# feszduplazo.net
KiCad netlist of a schematic drawn in EAGLE
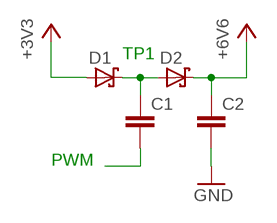
[diagram p0: schematic, sheet 1]

(export (version "E")
  (design (tool "Eeschema 10.0.6"))
  (components
    (comp (ref "C1")
      (value "C-EU050-024X044")
      (footprint "eagle-import:C050-024X044")
      (libsource (lib "eagle-import") (part "C-EU050-024X044"))
    )
    (comp (ref "C2")
      (value "C-EU050-024X044")
      (footprint "eagle-import:C050-024X044")
      (libsource (lib "eagle-import") (part "C-EU050-024X044"))
    )
    (comp (ref "D1")
      (value "1N5817-B")
      (footprint "eagle-import:DO41-7.6")
      (libsource (lib "eagle-import") (part "1N5817-B"))
    )
    (comp (ref "D2")
      (value "1N5817-B")
      (footprint "eagle-import:DO41-7.6")
      (libsource (lib "eagle-import") (part "1N5817-B"))
    )
  )
  (nets
    (net (code "1") (name "+3V3") (class "Default")
      (node (ref "D1") (pin "A") (pinfunction "A_A") (pintype "passive"))
    )
    (net (code "2") (name "+6V6") (class "Default")
      (node (ref "C2") (pin "1") (pinfunction "1_1") (pintype "passive"))
      (node (ref "D2") (pin "C") (pinfunction "C_C") (pintype "passive"))
    )
    (net (code "3") (name "GND") (class "Default")
      (node (ref "C2") (pin "2") (pinfunction "2_2") (pintype "passive"))
    )
    (net (code "4") (name "Net-(C1-Pad1)") (class "Default")
      (node (ref "C1") (pin "1") (pinfunction "1_1") (pintype "passive"))
      (node (ref "D1") (pin "C") (pinfunction "C_C") (pintype "passive"))
      (node (ref "D2") (pin "A") (pinfunction "A_A") (pintype "passive"))
    )
    (net (code "5") (name "unconnected-(C1-Pad2)") (class "Default")
      (node (ref "C1") (pin "2") (pinfunction "2_2") (pintype "passive"))
    )
  )
)
